# mainSheet.net
KiCad netlist of a schematic drawn in Altium Designer
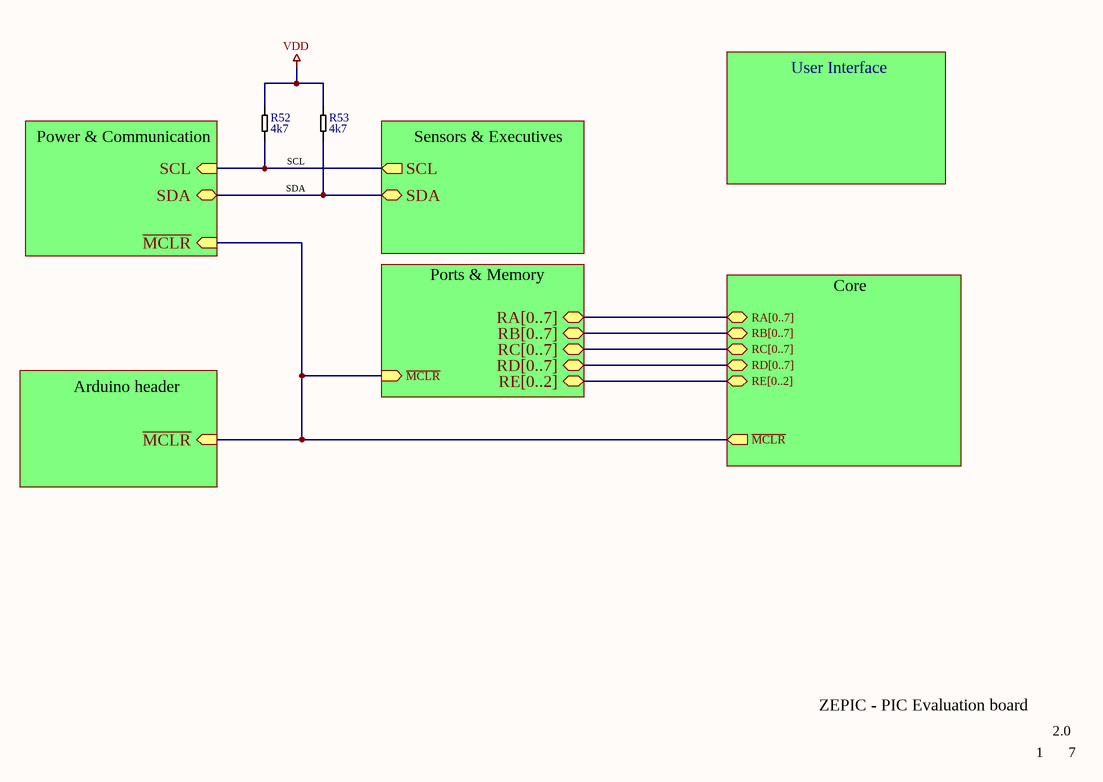
[diagram p0: mainSheet.SchDoc]

(export (version "E")
  (design (tool "Eeschema 10.0.6"))
  (components
    (comp (ref "R52")
      (value "Resistor")
      (footprint "0805")
      (fields (field (name "RESISTANCE") "4k7"))
      (libsource (lib "passive") (part "Resistor"))
    )
    (comp (ref "R53")
      (value "Resistor")
      (footprint "0805")
      (fields (field (name "RESISTANCE") "4k7"))
      (libsource (lib "passive") (part "Resistor"))
    )
  )
  (nets
    (net (code "6") (name "/SCL") (class "Default")
      (node (ref "R52") (pin "2") (pinfunction "2_2") (pintype "passive"))
    )
    (net (code "7") (name "/SDA") (class "Default")
      (node (ref "R53") (pin "2") (pinfunction "2_2") (pintype "passive"))
    )
    (net (code "9") (name "VDD") (class "Default")
      (node (ref "R52") (pin "1") (pinfunction "1_1") (pintype "passive"))
      (node (ref "R53") (pin "1") (pinfunction "1_1") (pintype "passive"))
    )
  )
)
